# simple_encoder.net
KiCad netlist of a schematic drawn in EAGLE
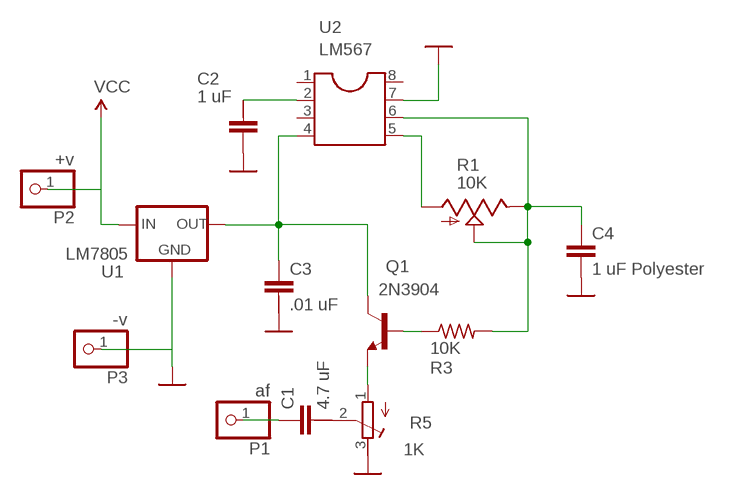
[diagram p0: schematic, sheet 1]

(export (version "E")
  (design (tool "Eeschema 10.0.6"))
  (components
    (comp (ref "C1")
      (value "4.7 uF")
      (footprint "eagle-import:C2.5_5-4")
      (libsource (lib "eagle-import") (part "C-2.5-5/4"))
    )
    (comp (ref "C2")
      (value "1 uF")
      (footprint "eagle-import:C2.5_5-2")
      (libsource (lib "eagle-import") (part "C-2.5-5/2"))
    )
    (comp (ref "C3")
      (value ".01 uF")
      (footprint "eagle-import:C2.5_5-2")
      (libsource (lib "eagle-import") (part "C-2.5-5/2"))
    )
    (comp (ref "C4")
      (value "1 uF Polyester")
      (footprint "eagle-import:C5B2.5")
      (libsource (lib "eagle-import") (part "C5/2.5"))
    )
    (comp (ref "P1")
      (value "af")
      (footprint "eagle-import:1X01")
      (libsource (lib "eagle-import") (part "PINHD-1X1"))
    )
    (comp (ref "P2")
      (value "+v")
      (footprint "eagle-import:1X01")
      (libsource (lib "eagle-import") (part "PINHD-1X1"))
    )
    (comp (ref "P3")
      (value "-v")
      (footprint "eagle-import:1X01")
      (libsource (lib "eagle-import") (part "PINHD-1X1"))
    )
    (comp (ref "Q1")
      (value "2N3904")
      (footprint "eagle-import:TO92")
      (libsource (lib "eagle-import") (part "2N3904"))
    )
    (comp (ref "R1")
      (value "10K")
      (footprint "eagle-import:S64W")
      (libsource (lib "eagle-import") (part "TRIM_US-S64W"))
    )
    (comp (ref "R3")
      (value "10K")
      (footprint "eagle-import:0204V")
      (libsource (lib "eagle-import") (part "R-US_0204/2V"))
    )
    (comp (ref "R5")
      (value "RTRIM-3362P")
      (footprint "eagle-import:RTRIM3362P")
      (libsource (lib "eagle-import") (part "RTRIM-3362P"))
    )
    (comp (ref "U1")
      (value "LM7805")
      (footprint "eagle-import:78LXX")
      (libsource (lib "eagle-import") (part "78LXX"))
    )
    (comp (ref "U2")
      (value "LM567")
      (footprint "eagle-import:DIL08")
      (libsource (lib "eagle-import") (part "DIL8"))
    )
  )
  (nets
    (net (code "1") (name "GND") (class "Default")
      (node (ref "C2") (pin "1") (pinfunction "1_1") (pintype "passive"))
      (node (ref "C3") (pin "2") (pinfunction "2_2") (pintype "passive"))
      (node (ref "C4") (pin "2") (pinfunction "2_2") (pintype "passive"))
      (node (ref "P3") (pin "1") (pinfunction "1_1") (pintype "passive"))
      (node (ref "R5") (pin "3") (pinfunction "3_3") (pintype "passive"))
      (node (ref "U1") (pin "GND") (pinfunction "GND_GND") (pintype "input"))
      (node (ref "U2") (pin "7") (pinfunction "7_7") (pintype "passive"))
    )
    (net (code "2") (name "Net-(C1-Pad1)") (class "Default")
      (node (ref "C1") (pin "1") (pinfunction "1_1") (pintype "passive"))
      (node (ref "P1") (pin "1") (pinfunction "1_1") (pintype "passive"))
    )
    (net (code "3") (name "Net-(C1-Pad2)") (class "Default")
      (node (ref "C1") (pin "2") (pinfunction "2_2") (pintype "passive"))
      (node (ref "R5") (pin "2") (pinfunction "2_2") (pintype "passive"))
    )
    (net (code "4") (name "Net-(C2-Pad2)") (class "Default")
      (node (ref "C2") (pin "2") (pinfunction "2_2") (pintype "passive"))
      (node (ref "U2") (pin "2") (pinfunction "2_2") (pintype "passive"))
    )
    (net (code "5") (name "Net-(C4-Pad1)") (class "Default")
      (node (ref "C4") (pin "1") (pinfunction "1_1") (pintype "passive"))
      (node (ref "R1") (pin "E") (pinfunction "E_E") (pintype "passive"))
      (node (ref "R1") (pin "S") (pinfunction "S_S") (pintype "passive"))
      (node (ref "R3") (pin "2") (pinfunction "2_2") (pintype "passive"))
      (node (ref "U2") (pin "6") (pinfunction "6_6") (pintype "passive"))
    )
    (net (code "6") (name "Net-(Q1-B)") (class "Default")
      (node (ref "Q1") (pin "2") (pinfunction "B_2") (pintype "passive"))
      (node (ref "R3") (pin "1") (pinfunction "1_1") (pintype "passive"))
    )
    (net (code "7") (name "Net-(Q1-C)") (class "Default")
      (node (ref "C3") (pin "1") (pinfunction "1_1") (pintype "passive"))
      (node (ref "Q1") (pin "1") (pinfunction "C_1") (pintype "passive"))
      (node (ref "U1") (pin "OUT") (pinfunction "OUT_OUT") (pintype "passive"))
      (node (ref "U2") (pin "4") (pinfunction "4_4") (pintype "passive"))
    )
    (net (code "8") (name "Net-(Q1-E)") (class "Default")
      (node (ref "Q1") (pin "3") (pinfunction "E_3") (pintype "passive"))
      (node (ref "R5") (pin "1") (pinfunction "1_1") (pintype "passive"))
    )
    (net (code "9") (name "Net-(R1-PadA)") (class "Default")
      (node (ref "R1") (pin "A") (pinfunction "A_A") (pintype "passive"))
      (node (ref "U2") (pin "5") (pinfunction "5_5") (pintype "passive"))
    )
    (net (code "10") (name "VCC") (class "Default")
      (node (ref "P2") (pin "1") (pinfunction "1_1") (pintype "passive"))
      (node (ref "U1") (pin "IN") (pinfunction "IN_IN") (pintype "input"))
    )
    (net (code "11") (name "unconnected-(C1-Pad3)") (class "Default")
      (node (ref "C1") (pin "3") (pinfunction "3_3") (pintype "passive"))
    )
    (net (code "12") (name "unconnected-(C2-Pad3)") (class "Default")
      (node (ref "C2") (pin "3") (pinfunction "3_3") (pintype "passive"))
    )
    (net (code "13") (name "unconnected-(C3-Pad3)") (class "Default")
      (node (ref "C3") (pin "3") (pinfunction "3_3") (pintype "passive"))
    )
    (net (code "14") (name "unconnected-(U2-Pad1)") (class "Default")
      (node (ref "U2") (pin "1") (pinfunction "1_1") (pintype "passive"))
    )
    (net (code "15") (name "unconnected-(U2-Pad3)") (class "Default")
      (node (ref "U2") (pin "3") (pinfunction "3_3") (pintype "passive"))
    )
    (net (code "16") (name "unconnected-(U2-Pad8)") (class "Default")
      (node (ref "U2") (pin "8") (pinfunction "8_8") (pintype "passive"))
    )
  )
)
